# Peripherals.net
KiCad netlist of a schematic drawn in Altium Designer
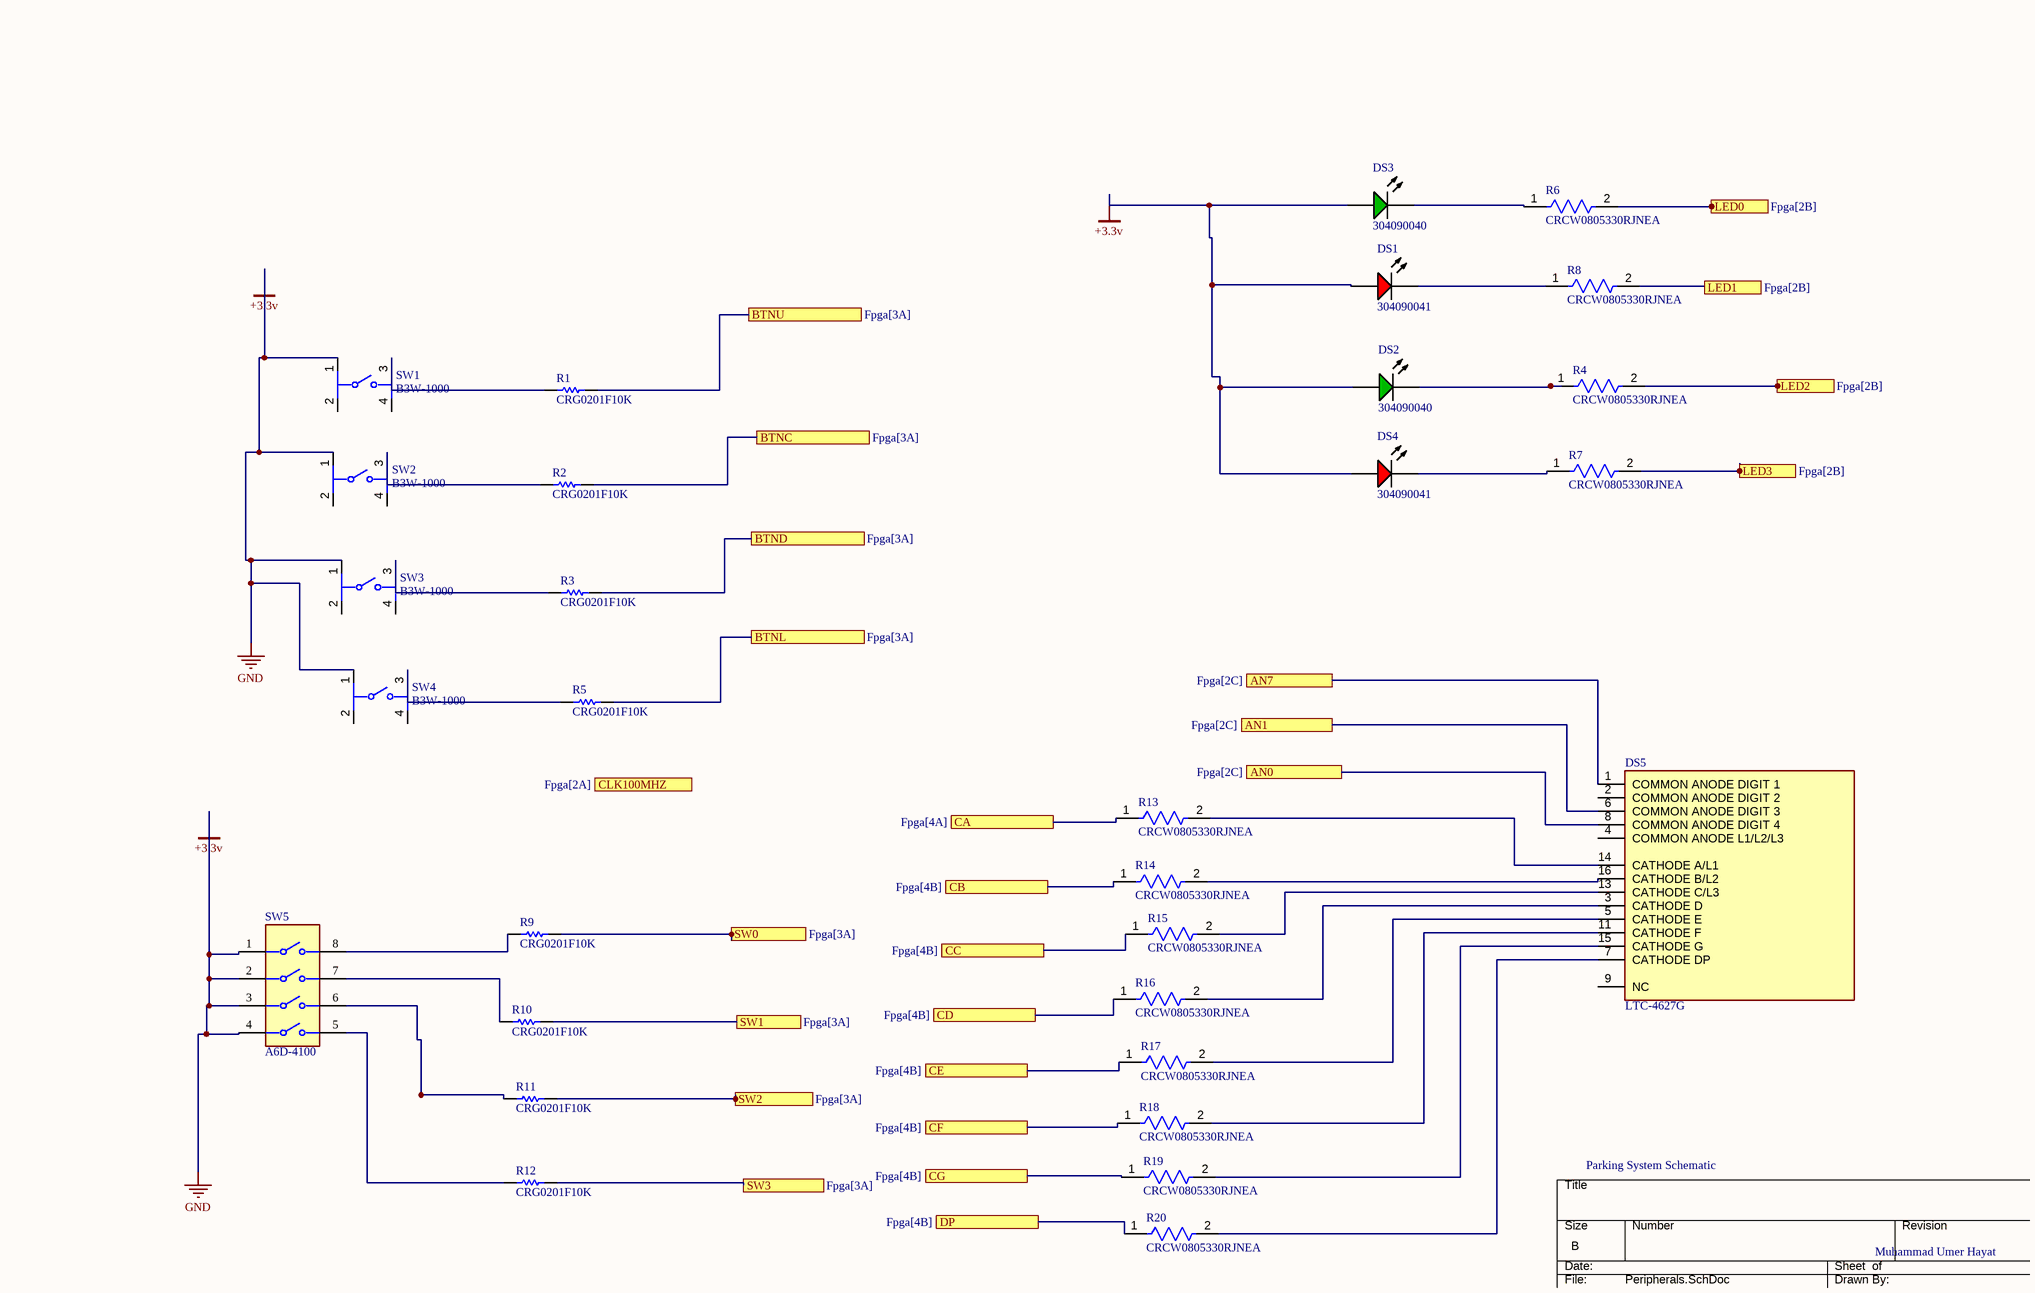
[diagram p0: Peripherals.SchDoc]

(export (version "E")
  (design (tool "Eeschema 10.0.6"))
  (components
    (comp (ref "DS1")
      (value "304090041")
      (footprint "LED-2P-2.28-3MM_A")
      (description "Red LED, 80 mW, 30 mA, -25 to 85 degC, 2-Pin THD")
      (fields (field (name "MANUFACTURER") "Shenzhen CGX"))
      (libsource (lib "Muhammad Umer Hayat") (part "LED-RED-AK-2"))
    )
    (comp (ref "DS2")
      (value "304090040")
      (footprint "LED-2P-2.28-3MM")
      (description "Green LED, 80 mW, 20 mA, -25 to 85 degC, 2-Pin THD")
      (fields (field (name "MANUFACTURER") "Shenzhen CGX"))
      (libsource (lib "Muhammad Umer Hayat") (part "LED-GREEN-AK-2"))
    )
    (comp (ref "DS3")
      (value "304090040")
      (footprint "LED-2P-2.28-3MM")
      (description "Green LED, 80 mW, 20 mA, -25 to 85 degC, 2-Pin THD")
      (fields (field (name "MANUFACTURER") "Shenzhen CGX"))
      (libsource (lib "Muhammad Umer Hayat") (part "LED-GREEN-AK-2"))
    )
    (comp (ref "DS4")
      (value "304090041")
      (footprint "LED-2P-2.28-3MM_A")
      (description "Red LED, 80 mW, 30 mA, -25 to 85 degC, 2-Pin THD")
      (fields (field (name "MANUFACTURER") "Shenzhen CGX"))
      (libsource (lib "Muhammad Umer Hayat") (part "LED-RED-AK-2"))
    )
    (comp (ref "DS5")
      (value "LTC-4627G")
      (footprint "FP-LTC-4627G-MFG")
      (description "LED 7-SEG 4DIGIT GRN 0.4\" CA")
      (fields
        (field (name "OCTOPART") "https://octopart.com/ltc-4627g-lite-on-8442722")
        (field (name "MANUFACTURER") "Lite-On")
      )
      (libsource (lib "Altium Content Vault") (part "4d055b40ff5d7e2a8d2cf02d3223e38"))
    )
    (comp (ref "R1")
      (value "CRG0201F10K")
      (footprint "RESC0603X26X15LL03T05")
      (fields (field (name "MANUFACTURER") "TE Connectivity / AMP"))
      (libsource (lib "Altium Content Vault") (part "RES"))
    )
    (comp (ref "R2")
      (value "CRG0201F10K")
      (footprint "RESC0603X26X15LL03T05")
      (fields (field (name "MANUFACTURER") "TE Connectivity / AMP"))
      (libsource (lib "Altium Content Vault") (part "RES"))
    )
    (comp (ref "R3")
      (value "CRG0201F10K")
      (footprint "RESC0603X26X15LL03T05")
      (fields (field (name "MANUFACTURER") "TE Connectivity / AMP"))
      (libsource (lib "Altium Content Vault") (part "RES"))
    )
    (comp (ref "R4")
      (value "CRCW0805330RJNEA")
      (footprint "FP-CRCW0805-e3-IPC_C")
      (description "RES Thick Film, 330Ω, 5%, 0.125W, 200ppm/°C, 0805")
      (fields (field (name "TOLERANCE") "5%"))
      (libsource (lib "Altium Content Vault") (part "1029c3af85768c4190bb7ad29bc67b5"))
    )
    (comp (ref "R5")
      (value "CRG0201F10K")
      (footprint "RESC0603X26X15LL03T05")
      (fields (field (name "MANUFACTURER") "TE Connectivity / AMP"))
      (libsource (lib "Altium Content Vault") (part "RES"))
    )
    (comp (ref "R6")
      (value "CRCW0805330RJNEA")
      (footprint "FP-CRCW0805-e3-IPC_C")
      (description "RES Thick Film, 330Ω, 5%, 0.125W, 200ppm/°C, 0805")
      (fields (field (name "TOLERANCE") "5%"))
      (libsource (lib "Altium Content Vault") (part "1029c3af85768c4190bb7ad29bc67b5"))
    )
    (comp (ref "R7")
      (value "CRCW0805330RJNEA")
      (footprint "FP-CRCW0805-e3-IPC_C")
      (description "RES Thick Film, 330Ω, 5%, 0.125W, 200ppm/°C, 0805")
      (fields (field (name "TOLERANCE") "5%"))
      (libsource (lib "Altium Content Vault") (part "1029c3af85768c4190bb7ad29bc67b5"))
    )
    (comp (ref "R8")
      (value "CRCW0805330RJNEA")
      (footprint "FP-CRCW0805-e3-IPC_C")
      (description "RES Thick Film, 330Ω, 5%, 0.125W, 200ppm/°C, 0805")
      (fields (field (name "TOLERANCE") "5%"))
      (libsource (lib "Altium Content Vault") (part "1029c3af85768c4190bb7ad29bc67b5"))
    )
    (comp (ref "R9")
      (value "CRG0201F10K")
      (footprint "RESC0603X26X15LL03T05")
      (fields (field (name "MANUFACTURER") "TE Connectivity / AMP"))
      (libsource (lib "Altium Content Vault") (part "RES"))
    )
    (comp (ref "R10")
      (value "CRG0201F10K")
      (footprint "RESC0603X26X15LL03T05")
      (fields (field (name "MANUFACTURER") "TE Connectivity / AMP"))
      (libsource (lib "Altium Content Vault") (part "RES"))
    )
    (comp (ref "R11")
      (value "CRG0201F10K")
      (footprint "RESC0603X26X15LL03T05")
      (fields (field (name "MANUFACTURER") "TE Connectivity / AMP"))
      (libsource (lib "Altium Content Vault") (part "RES"))
    )
    (comp (ref "R12")
      (value "CRG0201F10K")
      (footprint "RESC0603X26X15LL03T05")
      (fields (field (name "MANUFACTURER") "TE Connectivity / AMP"))
      (libsource (lib "Altium Content Vault") (part "RES"))
    )
    (comp (ref "R13")
      (value "CRCW0805330RJNEA")
      (footprint "FP-CRCW0805-e3-IPC_C")
      (description "RES Thick Film, 330Ω, 5%, 0.125W, 200ppm/°C, 0805")
      (fields (field (name "TOLERANCE") "5%"))
      (libsource (lib "Altium Content Vault") (part "1029c3af85768c4190bb7ad29bc67b5"))
    )
    (comp (ref "R14")
      (value "CRCW0805330RJNEA")
      (footprint "FP-CRCW0805-e3-IPC_C")
      (description "RES Thick Film, 330Ω, 5%, 0.125W, 200ppm/°C, 0805")
      (fields (field (name "TOLERANCE") "5%"))
      (libsource (lib "Altium Content Vault") (part "1029c3af85768c4190bb7ad29bc67b5"))
    )
    (comp (ref "R15")
      (value "CRCW0805330RJNEA")
      (footprint "FP-CRCW0805-e3-IPC_C")
      (description "RES Thick Film, 330Ω, 5%, 0.125W, 200ppm/°C, 0805")
      (fields (field (name "TOLERANCE") "5%"))
      (libsource (lib "Altium Content Vault") (part "1029c3af85768c4190bb7ad29bc67b5"))
    )
    (comp (ref "R16")
      (value "CRCW0805330RJNEA")
      (footprint "FP-CRCW0805-e3-IPC_C")
      (description "RES Thick Film, 330Ω, 5%, 0.125W, 200ppm/°C, 0805")
      (fields (field (name "TOLERANCE") "5%"))
      (libsource (lib "Altium Content Vault") (part "1029c3af85768c4190bb7ad29bc67b5"))
    )
    (comp (ref "R17")
      (value "CRCW0805330RJNEA")
      (footprint "FP-CRCW0805-e3-IPC_C")
      (description "RES Thick Film, 330Ω, 5%, 0.125W, 200ppm/°C, 0805")
      (fields (field (name "TOLERANCE") "5%"))
      (libsource (lib "Altium Content Vault") (part "1029c3af85768c4190bb7ad29bc67b5"))
    )
    (comp (ref "R18")
      (value "CRCW0805330RJNEA")
      (footprint "FP-CRCW0805-e3-IPC_C")
      (description "RES Thick Film, 330Ω, 5%, 0.125W, 200ppm/°C, 0805")
      (fields (field (name "TOLERANCE") "5%"))
      (libsource (lib "Altium Content Vault") (part "1029c3af85768c4190bb7ad29bc67b5"))
    )
    (comp (ref "R19")
      (value "CRCW0805330RJNEA")
      (footprint "FP-CRCW0805-e3-IPC_C")
      (description "RES Thick Film, 330Ω, 5%, 0.125W, 200ppm/°C, 0805")
      (fields (field (name "TOLERANCE") "5%"))
      (libsource (lib "Altium Content Vault") (part "1029c3af85768c4190bb7ad29bc67b5"))
    )
    (comp (ref "R20")
      (value "CRCW0805330RJNEA")
      (footprint "FP-CRCW0805-e3-IPC_C")
      (description "RES Thick Film, 330Ω, 5%, 0.125W, 200ppm/°C, 0805")
      (fields (field (name "TOLERANCE") "5%"))
      (libsource (lib "Altium Content Vault") (part "1029c3af85768c4190bb7ad29bc67b5"))
    )
    (comp (ref "SW1")
      (value "B3W-1000")
      (footprint "FP-B3W-1000-MFG")
      (description "SWITCH TACTILE SPST-NO 0.05A 24V")
      (libsource (lib "Altium Content Vault") (part "b8895f3f4cefb76e1819d2863dba89b"))
    )
    (comp (ref "SW2")
      (value "B3W-1000")
      (footprint "FP-B3W-1000-MFG")
      (description "SWITCH TACTILE SPST-NO 0.05A 24V")
      (libsource (lib "Altium Content Vault") (part "b8895f3f4cefb76e1819d2863dba89b"))
    )
    (comp (ref "SW3")
      (value "B3W-1000")
      (footprint "FP-B3W-1000-MFG")
      (description "SWITCH TACTILE SPST-NO 0.05A 24V")
      (libsource (lib "Altium Content Vault") (part "b8895f3f4cefb76e1819d2863dba89b"))
    )
    (comp (ref "SW4")
      (value "B3W-1000")
      (footprint "FP-B3W-1000-MFG")
      (description "SWITCH TACTILE SPST-NO 0.05A 24V")
      (libsource (lib "Altium Content Vault") (part "b8895f3f4cefb76e1819d2863dba89b"))
    )
    (comp (ref "SW5")
      (value "A6D-4100")
      (footprint "FP-A6D-4100-MFG")
      (description "SWITCH SLIDE DIP SPST 30MA 30V")
      (libsource (lib "Altium Content Vault") (part "cf9efd01ff2904b7e5ec5df82e72e71"))
    )
  )
  (nets
    (net (code "1") (name "+3.3v") (class "Default")
      (node (ref "DS1") (pin "1") (pinfunction "A_1") (pintype "passive"))
      (node (ref "DS2") (pin "1") (pinfunction "A_1") (pintype "passive"))
      (node (ref "DS3") (pin "1") (pinfunction "A_1") (pintype "passive"))
      (node (ref "DS4") (pin "1") (pinfunction "A_1") (pintype "passive"))
      (node (ref "SW1") (pin "1") (pinfunction "1_1") (pintype "passive"))
      (node (ref "SW2") (pin "1") (pinfunction "1_1") (pintype "passive"))
      (node (ref "SW3") (pin "1") (pinfunction "1_1") (pintype "passive"))
      (node (ref "SW4") (pin "1") (pinfunction "1_1") (pintype "passive"))
      (node (ref "SW5") (pin "1") (pinfunction "1_1") (pintype "passive"))
      (node (ref "SW5") (pin "2") (pinfunction "2_2") (pintype "passive"))
      (node (ref "SW5") (pin "3") (pinfunction "3_3") (pintype "passive"))
      (node (ref "SW5") (pin "4") (pinfunction "4_4") (pintype "passive"))
    )
    (net (code "2") (name "/AN0") (class "Default")
      (node (ref "DS5") (pin "8") (pinfunction "COMMON_ANODE_DIGIT_4_8") (pintype "passive"))
    )
    (net (code "3") (name "/AN1") (class "Default")
      (node (ref "DS5") (pin "6") (pinfunction "COMMON_ANODE_DIGIT_3_6") (pintype "passive"))
    )
    (net (code "4") (name "/AN7") (class "Default")
      (node (ref "DS5") (pin "1") (pinfunction "COMMON_ANODE_DIGIT_1_1") (pintype "passive"))
    )
    (net (code "5") (name "/BTNC") (class "Default")
      (node (ref "R2") (pin "2") (pinfunction "2_2") (pintype "passive"))
    )
    (net (code "6") (name "/BTND") (class "Default")
      (node (ref "R3") (pin "2") (pinfunction "2_2") (pintype "passive"))
    )
    (net (code "7") (name "/BTNL") (class "Default")
      (node (ref "R5") (pin "2") (pinfunction "2_2") (pintype "passive"))
    )
    (net (code "8") (name "/BTNU") (class "Default")
      (node (ref "R1") (pin "2") (pinfunction "2_2") (pintype "passive"))
    )
    (net (code "9") (name "/CA") (class "Default")
      (node (ref "R13") (pin "1") (pinfunction "1_1") (pintype "passive"))
    )
    (net (code "10") (name "/CB") (class "Default")
      (node (ref "R14") (pin "1") (pinfunction "1_1") (pintype "passive"))
    )
    (net (code "11") (name "/CC") (class "Default")
      (node (ref "R15") (pin "1") (pinfunction "1_1") (pintype "passive"))
    )
    (net (code "12") (name "/CD") (class "Default")
      (node (ref "R16") (pin "1") (pinfunction "1_1") (pintype "passive"))
    )
    (net (code "13") (name "/CE") (class "Default")
      (node (ref "R17") (pin "1") (pinfunction "1_1") (pintype "passive"))
    )
    (net (code "14") (name "/CF") (class "Default")
      (node (ref "R18") (pin "1") (pinfunction "1_1") (pintype "passive"))
    )
    (net (code "15") (name "/CG") (class "Default")
      (node (ref "R19") (pin "1") (pinfunction "1_1") (pintype "passive"))
    )
    (net (code "17") (name "/DP") (class "Default")
      (node (ref "R20") (pin "1") (pinfunction "1_1") (pintype "passive"))
    )
    (net (code "18") (name "/LED0") (class "Default")
      (node (ref "R6") (pin "2") (pinfunction "2_2") (pintype "passive"))
    )
    (net (code "19") (name "/LED1") (class "Default")
      (node (ref "R8") (pin "2") (pinfunction "2_2") (pintype "passive"))
    )
    (net (code "20") (name "/LED2") (class "Default")
      (node (ref "R4") (pin "2") (pinfunction "2_2") (pintype "passive"))
    )
    (net (code "21") (name "/LED3") (class "Default")
      (node (ref "R7") (pin "2") (pinfunction "2_2") (pintype "passive"))
    )
    (net (code "22") (name "/SW0") (class "Default")
      (node (ref "R9") (pin "2") (pinfunction "2_2") (pintype "passive"))
    )
    (net (code "23") (name "/SW1") (class "Default")
      (node (ref "R10") (pin "2") (pinfunction "2_2") (pintype "passive"))
    )
    (net (code "24") (name "/SW2") (class "Default")
      (node (ref "R11") (pin "2") (pinfunction "2_2") (pintype "passive"))
    )
    (net (code "25") (name "/SW3") (class "Default")
      (node (ref "R12") (pin "2") (pinfunction "2_2") (pintype "passive"))
    )
    (net (code "26") (name "Net-(DS1-K)") (class "Default")
      (node (ref "DS1") (pin "2") (pinfunction "K_2") (pintype "passive"))
      (node (ref "R8") (pin "1") (pinfunction "1_1") (pintype "passive"))
    )
    (net (code "27") (name "Net-(DS2-K)") (class "Default")
      (node (ref "DS2") (pin "2") (pinfunction "K_2") (pintype "passive"))
      (node (ref "R4") (pin "1") (pinfunction "1_1") (pintype "passive"))
    )
    (net (code "28") (name "Net-(DS3-K)") (class "Default")
      (node (ref "DS3") (pin "2") (pinfunction "K_2") (pintype "passive"))
      (node (ref "R6") (pin "1") (pinfunction "1_1") (pintype "passive"))
    )
    (net (code "29") (name "Net-(DS4-K)") (class "Default")
      (node (ref "DS4") (pin "2") (pinfunction "K_2") (pintype "passive"))
      (node (ref "R7") (pin "1") (pinfunction "1_1") (pintype "passive"))
    )
    (net (code "30") (name "Net-(DS5-CATHODE_A{slash}L1)") (class "Default")
      (node (ref "DS5") (pin "14") (pinfunction "CATHODE_A/L1_14") (pintype "passive"))
      (node (ref "R13") (pin "2") (pinfunction "2_2") (pintype "passive"))
    )
    (net (code "31") (name "Net-(DS5-CATHODE_B{slash}L2)") (class "Default")
      (node (ref "DS5") (pin "16") (pinfunction "CATHODE_B/L2_16") (pintype "passive"))
      (node (ref "R14") (pin "2") (pinfunction "2_2") (pintype "passive"))
    )
    (net (code "32") (name "Net-(DS5-CATHODE_C{slash}L3)") (class "Default")
      (node (ref "DS5") (pin "13") (pinfunction "CATHODE_C/L3_13") (pintype "passive"))
      (node (ref "R15") (pin "2") (pinfunction "2_2") (pintype "passive"))
    )
    (net (code "33") (name "Net-(DS5-CATHODE_D)") (class "Default")
      (node (ref "DS5") (pin "3") (pinfunction "CATHODE_D_3") (pintype "passive"))
      (node (ref "R16") (pin "2") (pinfunction "2_2") (pintype "passive"))
    )
    (net (code "34") (name "Net-(DS5-CATHODE_DP)") (class "Default")
      (node (ref "DS5") (pin "7") (pinfunction "CATHODE_DP_7") (pintype "passive"))
      (node (ref "R20") (pin "2") (pinfunction "2_2") (pintype "passive"))
    )
    (net (code "35") (name "Net-(DS5-CATHODE_E)") (class "Default")
      (node (ref "DS5") (pin "5") (pinfunction "CATHODE_E_5") (pintype "passive"))
      (node (ref "R17") (pin "2") (pinfunction "2_2") (pintype "passive"))
    )
    (net (code "36") (name "Net-(DS5-CATHODE_F)") (class "Default")
      (node (ref "DS5") (pin "11") (pinfunction "CATHODE_F_11") (pintype "passive"))
      (node (ref "R18") (pin "2") (pinfunction "2_2") (pintype "passive"))
    )
    (net (code "37") (name "Net-(DS5-CATHODE_G)") (class "Default")
      (node (ref "DS5") (pin "15") (pinfunction "CATHODE_G_15") (pintype "passive"))
      (node (ref "R19") (pin "2") (pinfunction "2_2") (pintype "passive"))
    )
    (net (code "38") (name "Net-(R1-Pad1)") (class "Default")
      (node (ref "R1") (pin "1") (pinfunction "1_1") (pintype "passive"))
      (node (ref "SW1") (pin "3") (pinfunction "3_3") (pintype "passive"))
    )
    (net (code "39") (name "Net-(R2-Pad1)") (class "Default")
      (node (ref "R2") (pin "1") (pinfunction "1_1") (pintype "passive"))
      (node (ref "SW2") (pin "3") (pinfunction "3_3") (pintype "passive"))
    )
    (net (code "40") (name "Net-(R3-Pad1)") (class "Default")
      (node (ref "R3") (pin "1") (pinfunction "1_1") (pintype "passive"))
      (node (ref "SW3") (pin "3") (pinfunction "3_3") (pintype "passive"))
    )
    (net (code "41") (name "Net-(R5-Pad1)") (class "Default")
      (node (ref "R5") (pin "1") (pinfunction "1_1") (pintype "passive"))
      (node (ref "SW4") (pin "3") (pinfunction "3_3") (pintype "passive"))
    )
    (net (code "42") (name "Net-(R9-Pad1)") (class "Default")
      (node (ref "R9") (pin "1") (pinfunction "1_1") (pintype "passive"))
      (node (ref "SW5") (pin "8") (pinfunction "8_8") (pintype "passive"))
    )
    (net (code "43") (name "Net-(R10-Pad1)") (class "Default")
      (node (ref "R10") (pin "1") (pinfunction "1_1") (pintype "passive"))
      (node (ref "SW5") (pin "7") (pinfunction "7_7") (pintype "passive"))
    )
    (net (code "44") (name "Net-(R11-Pad1)") (class "Default")
      (node (ref "R11") (pin "1") (pinfunction "1_1") (pintype "passive"))
      (node (ref "SW5") (pin "6") (pinfunction "6_6") (pintype "passive"))
    )
    (net (code "45") (name "Net-(R12-Pad1)") (class "Default")
      (node (ref "R12") (pin "1") (pinfunction "1_1") (pintype "passive"))
      (node (ref "SW5") (pin "5") (pinfunction "5_5") (pintype "passive"))
    )
    (net (code "46") (name "unconnected-(DS5-COMMON_ANODE_DIGIT_2-Pad2)") (class "Default")
      (node (ref "DS5") (pin "2") (pinfunction "COMMON_ANODE_DIGIT_2_2") (pintype "passive"))
    )
    (net (code "47") (name "unconnected-(DS5-COMMON_ANODE_L1{slash}L2{slash}L3-Pad4)") (class "Default")
      (node (ref "DS5") (pin "4") (pinfunction "COMMON_ANODE_L1/L2/L3_4") (pintype "passive"))
    )
    (net (code "48") (name "unconnected-(DS5-NC-Pad9)") (class "Default")
      (node (ref "DS5") (pin "9") (pinfunction "NC_9") (pintype "passive"))
    )
    (net (code "49") (name "unconnected-(SW1-Pad2)") (class "Default")
      (node (ref "SW1") (pin "2") (pinfunction "2_2") (pintype "passive"))
    )
    (net (code "50") (name "unconnected-(SW1-Pad4)") (class "Default")
      (node (ref "SW1") (pin "4") (pinfunction "4_4") (pintype "passive"))
    )
    (net (code "51") (name "unconnected-(SW2-Pad2)") (class "Default")
      (node (ref "SW2") (pin "2") (pinfunction "2_2") (pintype "passive"))
    )
    (net (code "52") (name "unconnected-(SW2-Pad4)") (class "Default")
      (node (ref "SW2") (pin "4") (pinfunction "4_4") (pintype "passive"))
    )
    (net (code "53") (name "unconnected-(SW3-Pad2)") (class "Default")
      (node (ref "SW3") (pin "2") (pinfunction "2_2") (pintype "passive"))
    )
    (net (code "54") (name "unconnected-(SW3-Pad4)") (class "Default")
      (node (ref "SW3") (pin "4") (pinfunction "4_4") (pintype "passive"))
    )
    (net (code "55") (name "unconnected-(SW4-Pad2)") (class "Default")
      (node (ref "SW4") (pin "2") (pinfunction "2_2") (pintype "passive"))
    )
    (net (code "56") (name "unconnected-(SW4-Pad4)") (class "Default")
      (node (ref "SW4") (pin "4") (pinfunction "4_4") (pintype "passive"))
    )
  )
)
